# first_1.net
KiCad netlist of a schematic drawn in Altium Designer
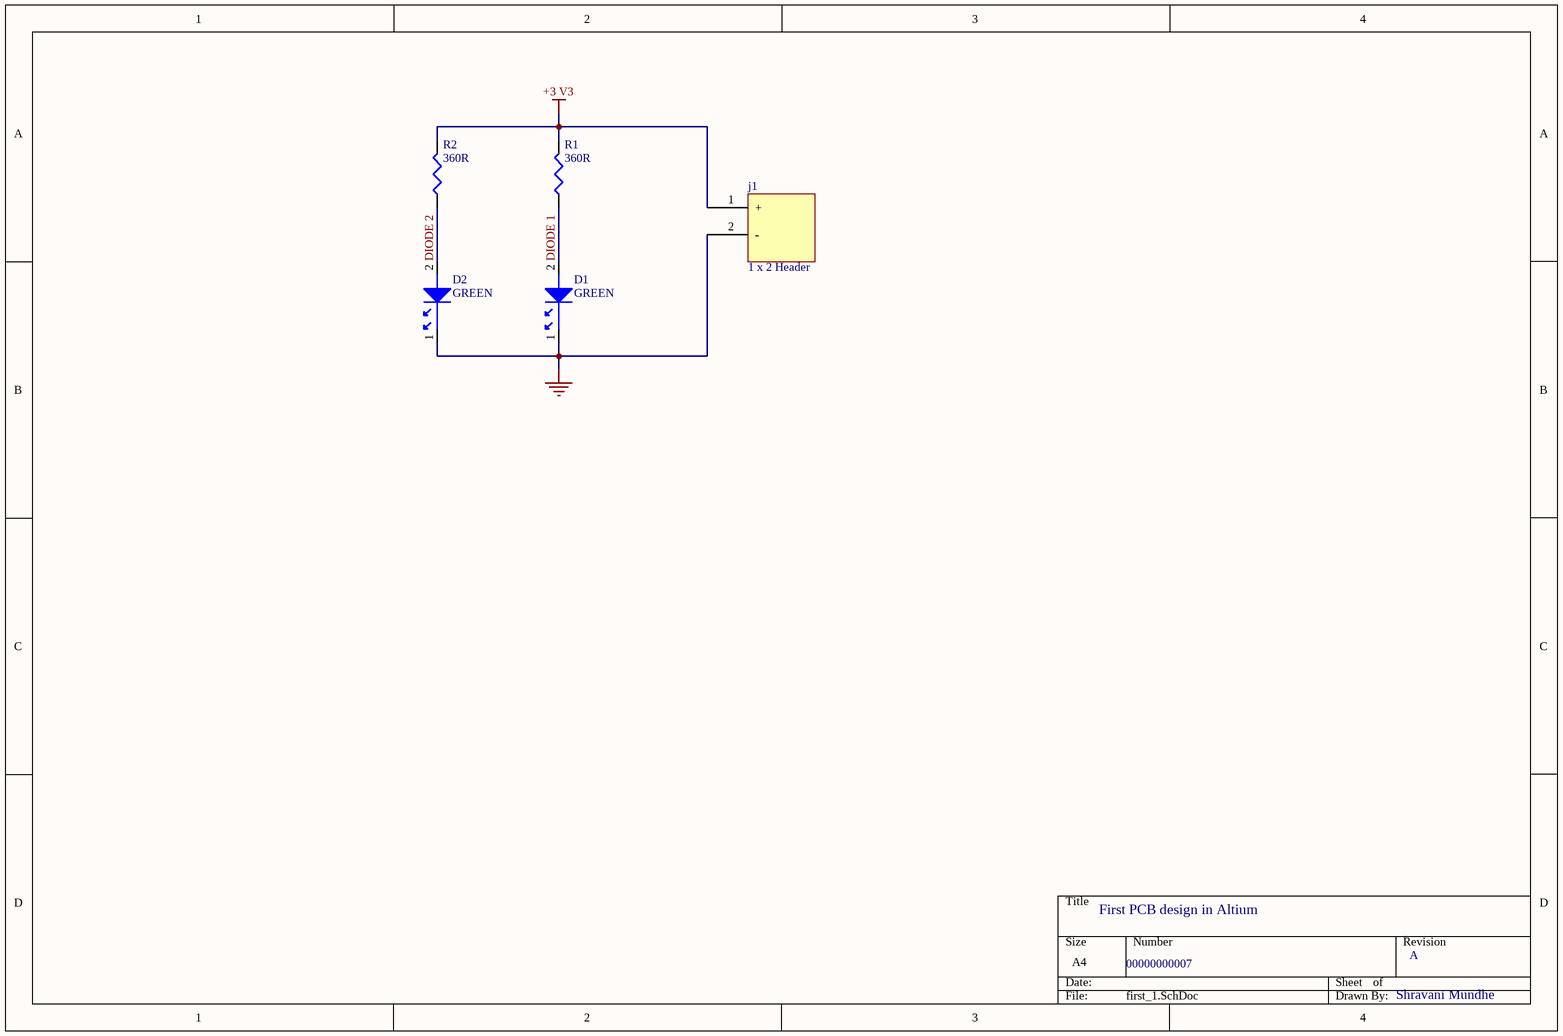
[diagram p0: first_1.SchDoc]

(export (version "E")
  (design (tool "Eeschema 10.0.6"))
  (components
    (comp (ref "D1")
      (value "GREEN")
      (footprint "LED0603G")
      (description "LED GREEN CLEAR CHIP 0603 SMD")
      (fields
        (field (name "MANUFACTURER") "Visual Communications")
        (field (name "MANUFACTURER PART NUMBER") "LSM0603453V")
      )
      (libsource (lib "LED_Schlib1") (part "LSM0603453V"))
    )
    (comp (ref "D2")
      (value "GREEN")
      (footprint "LED0603G")
      (description "LED GREEN CLEAR CHIP 0603 SMD")
      (fields
        (field (name "MANUFACTURER") "Visual Communications")
        (field (name "MANUFACTURER PART NUMBER") "LSM0603453V")
      )
      (libsource (lib "LED_Schlib1") (part "LSM0603453V"))
    )
    (comp (ref "j1")
      (value "1 x 2 Header")
      (footprint "HDR1X2")
      (description "Connector Header Through Hole 2 position 0.100\" (2.54mm)")
      (fields (field (name "MANUFACTURER") "Molex") (field (name "MANUFACTURER PART NUMBER") "22-27-2021"))
      (libsource (lib "LED_Schlib1") (part "22-27-2021 (3)"))
    )
    (comp (ref "R1")
      (value "360R")
      (footprint "R0805")
      (description "RES SMD 360 OHM 1% 1/8W 0805")
      (fields
        (field (name "MANUFACTURER") "Yageo")
        (field (name "MANUFACTURER PART NUMBER") "AC0805FR-07360RL")
      )
      (libsource (lib "LED_Schlib1") (part "AC0805FR-07360RL"))
    )
    (comp (ref "R2")
      (value "360R")
      (footprint "R0805")
      (description "RES SMD 360 OHM 1% 1/8W 0805")
      (fields
        (field (name "MANUFACTURER") "Yageo")
        (field (name "MANUFACTURER PART NUMBER") "AC0805FR-07360RL")
      )
      (libsource (lib "LED_Schlib1") (part "AC0805FR-07360RL"))
    )
  )
  (nets
    (net (code "1") (name "+3 V3") (class "Default")
      (node (ref "R1") (pin "2") (pinfunction "2_2") (pintype "passive"))
      (node (ref "R2") (pin "2") (pinfunction "2_2") (pintype "passive"))
      (node (ref "j1") (pin "1") (pinfunction "+_1") (pintype "passive"))
    )
    (net (code "2") (name "/DIODE 1") (class "Default")
      (node (ref "D1") (pin "2") (pinfunction "2_2") (pintype "passive"))
      (node (ref "R1") (pin "1") (pinfunction "1_1") (pintype "passive"))
    )
    (net (code "3") (name "/DIODE 2") (class "Default")
      (node (ref "D2") (pin "2") (pinfunction "2_2") (pintype "passive"))
      (node (ref "R2") (pin "1") (pinfunction "1_1") (pintype "passive"))
    )
    (net (code "4") (name "GND") (class "Default")
      (node (ref "D1") (pin "1") (pinfunction "1_1") (pintype "passive"))
      (node (ref "D2") (pin "1") (pinfunction "1_1") (pintype "passive"))
      (node (ref "j1") (pin "2") (pinfunction "-_2") (pintype "passive"))
    )
  )
)
